# FN_001.net
KiCad netlist of a schematic drawn in EAGLE
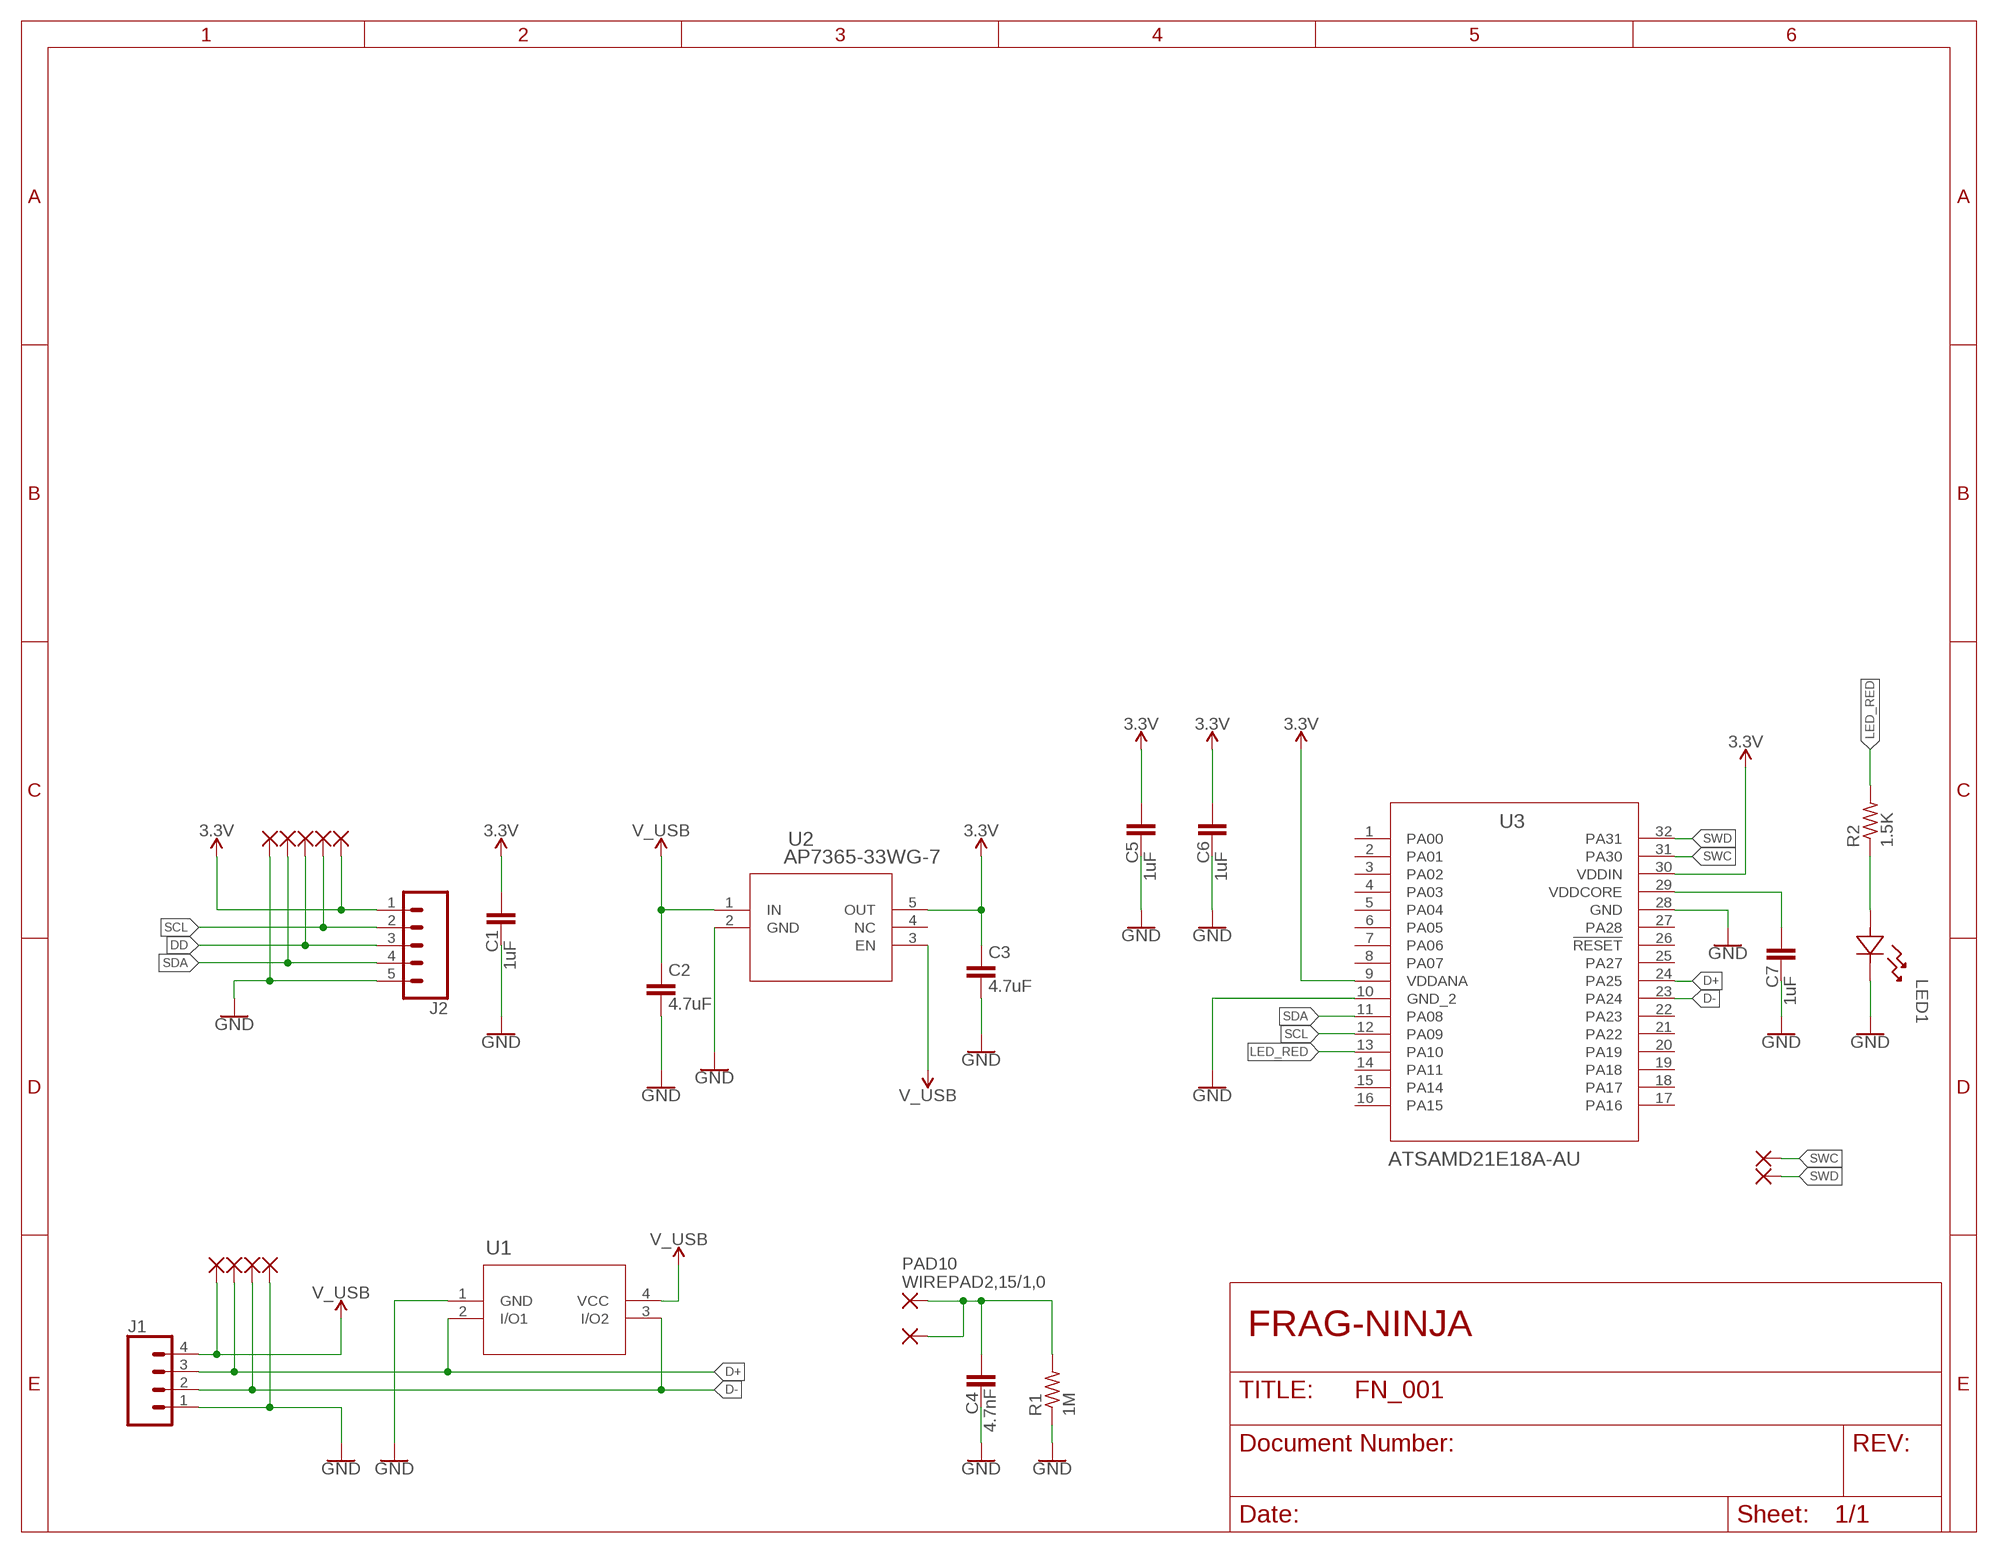
[diagram p0: schematic, sheet 1]

(export (version "E")
  (design (tool "Eeschema 10.0.6"))
  (components
    (comp (ref "C1")
      (value "1uF")
      (footprint "eagle-import:C0603K")
      (libsource (lib "eagle-import") (part "C-EUC0603K"))
    )
    (comp (ref "C2")
      (value "4.7uF")
      (footprint "eagle-import:C0603K")
      (libsource (lib "eagle-import") (part "C-EUC0603K"))
    )
    (comp (ref "C3")
      (value "4.7uF")
      (footprint "eagle-import:C0603K")
      (libsource (lib "eagle-import") (part "C-EUC0603K"))
    )
    (comp (ref "C4")
      (value "4.7nF")
      (footprint "eagle-import:C0603K")
      (libsource (lib "eagle-import") (part "C-EUC0603K"))
    )
    (comp (ref "C5")
      (value "1uF")
      (footprint "eagle-import:C0603K")
      (libsource (lib "eagle-import") (part "C-EUC0603K"))
    )
    (comp (ref "C6")
      (value "1uF")
      (footprint "eagle-import:C0603K")
      (libsource (lib "eagle-import") (part "C-EUC0603K"))
    )
    (comp (ref "C7")
      (value "1uF")
      (footprint "eagle-import:C0603K")
      (libsource (lib "eagle-import") (part "C-EUC0603K"))
    )
    (comp (ref "J1")
      (value "CONN_04PTH")
      (footprint "eagle-import:1X04")
      (libsource (lib "eagle-import") (part "CONN_04PTH"))
    )
    (comp (ref "J2")
      (value "CONN_05")
      (footprint "eagle-import:1X05")
      (libsource (lib "eagle-import") (part "CONN_05"))
    )
    (comp (ref "LED1")
      (value "SML-D12U1WT86")
      (footprint "eagle-import:LED_SMLD12_ROM")
      (fields (field (name "COPYRIGHT") "Copyright (C) 2018 Accelerated Designs. All rights reserved"))
      (libsource (lib "eagle-import") (part "SML-D12U1WT86"))
    )
    (comp (ref "PAD1")
      (value "WIREPADSMD1,27-254")
      (footprint "eagle-import:SMD1,27-2,54")
      (libsource (lib "eagle-import") (part "WIREPADSMD1,27-254"))
    )
    (comp (ref "PAD2")
      (value "WIREPADSMD1,27-254")
      (footprint "eagle-import:SMD1,27-2,54")
      (libsource (lib "eagle-import") (part "WIREPADSMD1,27-254"))
    )
    (comp (ref "PAD3")
      (value "WIREPADSMD1,27-254")
      (footprint "eagle-import:SMD1,27-2,54")
      (libsource (lib "eagle-import") (part "WIREPADSMD1,27-254"))
    )
    (comp (ref "PAD4")
      (value "WIREPADSMD1,27-254")
      (footprint "eagle-import:SMD1,27-2,54")
      (libsource (lib "eagle-import") (part "WIREPADSMD1,27-254"))
    )
    (comp (ref "PAD5")
      (value "WIREPADSMD1,27-254")
      (footprint "eagle-import:SMD1,27-2,54")
      (libsource (lib "eagle-import") (part "WIREPADSMD1,27-254"))
    )
    (comp (ref "PAD6")
      (value "WIREPADSMD1,27-254")
      (footprint "eagle-import:SMD1,27-2,54")
      (libsource (lib "eagle-import") (part "WIREPADSMD1,27-254"))
    )
    (comp (ref "PAD7")
      (value "WIREPADSMD1,27-254")
      (footprint "eagle-import:SMD1,27-2,54")
      (libsource (lib "eagle-import") (part "WIREPADSMD1,27-254"))
    )
    (comp (ref "PAD8")
      (value "WIREPADSMD1,27-254")
      (footprint "eagle-import:SMD1,27-2,54")
      (libsource (lib "eagle-import") (part "WIREPADSMD1,27-254"))
    )
    (comp (ref "PAD9")
      (value "WIREPADSMD1,27-254")
      (footprint "eagle-import:SMD1,27-2,54")
      (libsource (lib "eagle-import") (part "WIREPADSMD1,27-254"))
    )
    (comp (ref "PAD10")
      (value "WIREPAD2,15/1,0")
      (footprint "eagle-import:2,15_1,0")
      (libsource (lib "eagle-import") (part "WIREPAD2,15/1,0"))
    )
    (comp (ref "PAD11")
      (value "WIREPADSMD2,54-5,08")
      (footprint "eagle-import:SMD2,54-5,08")
      (libsource (lib "eagle-import") (part "WIREPADSMD2,54-5,08"))
    )
    (comp (ref "PAD12")
      (value "WIREPADSMD1,27-254")
      (footprint "eagle-import:SMD1,27-2,54")
      (libsource (lib "eagle-import") (part "WIREPADSMD1,27-254"))
    )
    (comp (ref "PAD13")
      (value "WIREPADSMD1,27-254")
      (footprint "eagle-import:SMD1,27-2,54")
      (libsource (lib "eagle-import") (part "WIREPADSMD1,27-254"))
    )
    (comp (ref "R1")
      (value "1M")
      (footprint "eagle-import:R0603")
      (libsource (lib "eagle-import") (part "R-US_R0603"))
    )
    (comp (ref "R2")
      (value "1.5K")
      (footprint "eagle-import:R0603")
      (libsource (lib "eagle-import") (part "R-US_R0603"))
    )
    (comp (ref "U1")
      (value "PRTR5V0U2X")
      (footprint "eagle-import:SOT143B_NXP")
      (libsource (lib "eagle-import") (part "PRTR5V0U2X"))
    )
    (comp (ref "U2")
      (value "AP7365-33WG-7")
      (footprint "eagle-import:SOT25_DIO")
      (libsource (lib "eagle-import") (part "AP7365-33WG-7"))
    )
    (comp (ref "U3")
      (value "ATSAMD21E18A-AU")
      (footprint "eagle-import:TQFP32_MC_MCH")
      (fields (field (name "COPYRIGHT") "Copyright (C) 2018 Accelerated Designs. All rights reserved"))
      (libsource (lib "eagle-import") (part "ATSAMD21E18A-AU"))
    )
  )
  (nets
    (net (code "1") (name "3.3V") (class "Default")
      (node (ref "C1") (pin "1") (pinfunction "1_1") (pintype "passive"))
      (node (ref "C3") (pin "1") (pinfunction "1_1") (pintype "passive"))
      (node (ref "C5") (pin "1") (pinfunction "1_1") (pintype "passive"))
      (node (ref "C6") (pin "1") (pinfunction "1_1") (pintype "passive"))
      (node (ref "J2") (pin "1") (pinfunction "1_1") (pintype "passive"))
      (node (ref "PAD9") (pin "1") (pinfunction "P_1") (pintype "passive"))
      (node (ref "U2") (pin "5") (pinfunction "OUT_5") (pintype "output"))
      (node (ref "U3") (pin "30") (pinfunction "VDDIN_30") (pintype "power_in"))
      (node (ref "U3") (pin "9") (pinfunction "VDDANA_9") (pintype "power_in"))
    )
    (net (code "2") (name "D+") (class "Default")
      (node (ref "J1") (pin "3") (pinfunction "3_3") (pintype "passive"))
      (node (ref "PAD2") (pin "1") (pinfunction "P_1") (pintype "passive"))
      (node (ref "U1") (pin "2") (pinfunction "I/O1_2") (pintype "passive"))
      (node (ref "U3") (pin "24") (pinfunction "PA25_24") (pintype "bidirectional"))
    )
    (net (code "3") (name "D-") (class "Default")
      (node (ref "J1") (pin "2") (pinfunction "2_2") (pintype "passive"))
      (node (ref "PAD3") (pin "1") (pinfunction "P_1") (pintype "passive"))
      (node (ref "U1") (pin "3") (pinfunction "I/O2_3") (pintype "passive"))
      (node (ref "U3") (pin "23") (pinfunction "PA24_23") (pintype "bidirectional"))
    )
    (net (code "4") (name "DD") (class "Default")
      (node (ref "J2") (pin "3") (pinfunction "3_3") (pintype "passive"))
      (node (ref "PAD7") (pin "1") (pinfunction "P_1") (pintype "passive"))
    )
    (net (code "5") (name "GND") (class "Default")
      (node (ref "C1") (pin "2") (pinfunction "2_2") (pintype "passive"))
      (node (ref "C2") (pin "2") (pinfunction "2_2") (pintype "passive"))
      (node (ref "C3") (pin "2") (pinfunction "2_2") (pintype "passive"))
      (node (ref "C4") (pin "2") (pinfunction "2_2") (pintype "passive"))
      (node (ref "C5") (pin "2") (pinfunction "2_2") (pintype "passive"))
      (node (ref "C6") (pin "2") (pinfunction "2_2") (pintype "passive"))
      (node (ref "C7") (pin "2") (pinfunction "2_2") (pintype "passive"))
      (node (ref "J1") (pin "1") (pinfunction "1_1") (pintype "passive"))
      (node (ref "J2") (pin "5") (pinfunction "5_5") (pintype "passive"))
      (node (ref "LED1") (pin "1") (pinfunction "1_1") (pintype "passive"))
      (node (ref "PAD4") (pin "1") (pinfunction "P_1") (pintype "passive"))
      (node (ref "PAD5") (pin "1") (pinfunction "P_1") (pintype "passive"))
      (node (ref "R1") (pin "1") (pinfunction "1_1") (pintype "passive"))
      (node (ref "U1") (pin "1") (pinfunction "GND_1") (pintype "passive"))
      (node (ref "U2") (pin "2") (pinfunction "GND_2") (pintype "power_in"))
      (node (ref "U3") (pin "10") (pinfunction "GND_2_10") (pintype "passive"))
      (node (ref "U3") (pin "28") (pinfunction "GND_28") (pintype "passive"))
    )
    (net (code "6") (name "LED_RED") (class "Default")
      (node (ref "R2") (pin "2") (pinfunction "2_2") (pintype "passive"))
      (node (ref "U3") (pin "13") (pinfunction "PA10_13") (pintype "bidirectional"))
    )
    (net (code "7") (name "Net-(LED1-Pad2)") (class "Default")
      (node (ref "LED1") (pin "2") (pinfunction "2_2") (pintype "passive"))
      (node (ref "R2") (pin "1") (pinfunction "1_1") (pintype "passive"))
    )
    (net (code "8") (name "Net-(PAD10-P)") (class "Default")
      (node (ref "C4") (pin "1") (pinfunction "1_1") (pintype "passive"))
      (node (ref "PAD10") (pin "1") (pinfunction "P_1") (pintype "passive"))
      (node (ref "PAD11") (pin "1") (pinfunction "P_1") (pintype "passive"))
      (node (ref "R1") (pin "2") (pinfunction "2_2") (pintype "passive"))
    )
    (net (code "9") (name "Net-(U3-VDDCORE)") (class "Default")
      (node (ref "C7") (pin "1") (pinfunction "1_1") (pintype "passive"))
      (node (ref "U3") (pin "29") (pinfunction "VDDCORE_29") (pintype "power_in"))
    )
    (net (code "10") (name "SCL") (class "Default")
      (node (ref "J2") (pin "2") (pinfunction "2_2") (pintype "passive"))
      (node (ref "PAD8") (pin "1") (pinfunction "P_1") (pintype "passive"))
      (node (ref "U3") (pin "12") (pinfunction "PA09_12") (pintype "bidirectional"))
    )
    (net (code "11") (name "SDA") (class "Default")
      (node (ref "J2") (pin "4") (pinfunction "4_4") (pintype "passive"))
      (node (ref "PAD6") (pin "1") (pinfunction "P_1") (pintype "passive"))
      (node (ref "U3") (pin "11") (pinfunction "PA08_11") (pintype "bidirectional"))
    )
    (net (code "12") (name "SWC") (class "Default")
      (node (ref "PAD12") (pin "1") (pinfunction "P_1") (pintype "passive"))
      (node (ref "U3") (pin "31") (pinfunction "PA30_31") (pintype "bidirectional"))
    )
    (net (code "13") (name "SWD") (class "Default")
      (node (ref "PAD13") (pin "1") (pinfunction "P_1") (pintype "passive"))
      (node (ref "U3") (pin "32") (pinfunction "PA31_32") (pintype "bidirectional"))
    )
    (net (code "14") (name "V_USB") (class "Default")
      (node (ref "C2") (pin "1") (pinfunction "1_1") (pintype "passive"))
      (node (ref "J1") (pin "4") (pinfunction "4_4") (pintype "passive"))
      (node (ref "PAD1") (pin "1") (pinfunction "P_1") (pintype "passive"))
      (node (ref "U1") (pin "4") (pinfunction "VCC_4") (pintype "passive"))
      (node (ref "U2") (pin "1") (pinfunction "IN_1") (pintype "input"))
      (node (ref "U2") (pin "3") (pinfunction "EN_3") (pintype "input"))
    )
    (net (code "15") (name "unconnected-(U2-NC-Pad4)") (class "Default")
      (node (ref "U2") (pin "4") (pinfunction "NC_4") (pintype "no_connect"))
    )
    (net (code "16") (name "unconnected-(U3-PA00-Pad1)") (class "Default")
      (node (ref "U3") (pin "1") (pinfunction "PA00_1") (pintype "bidirectional"))
    )
    (net (code "17") (name "unconnected-(U3-PA01-Pad2)") (class "Default")
      (node (ref "U3") (pin "2") (pinfunction "PA01_2") (pintype "bidirectional"))
    )
    (net (code "18") (name "unconnected-(U3-PA02-Pad3)") (class "Default")
      (node (ref "U3") (pin "3") (pinfunction "PA02_3") (pintype "bidirectional"))
    )
    (net (code "19") (name "unconnected-(U3-PA03-Pad4)") (class "Default")
      (node (ref "U3") (pin "4") (pinfunction "PA03_4") (pintype "bidirectional"))
    )
    (net (code "20") (name "unconnected-(U3-PA04-Pad5)") (class "Default")
      (node (ref "U3") (pin "5") (pinfunction "PA04_5") (pintype "bidirectional"))
    )
    (net (code "21") (name "unconnected-(U3-PA05-Pad6)") (class "Default")
      (node (ref "U3") (pin "6") (pinfunction "PA05_6") (pintype "bidirectional"))
    )
    (net (code "22") (name "unconnected-(U3-PA06-Pad7)") (class "Default")
      (node (ref "U3") (pin "7") (pinfunction "PA06_7") (pintype "bidirectional"))
    )
    (net (code "23") (name "unconnected-(U3-PA07-Pad8)") (class "Default")
      (node (ref "U3") (pin "8") (pinfunction "PA07_8") (pintype "bidirectional"))
    )
    (net (code "24") (name "unconnected-(U3-PA11-Pad14)") (class "Default")
      (node (ref "U3") (pin "14") (pinfunction "PA11_14") (pintype "bidirectional"))
    )
    (net (code "25") (name "unconnected-(U3-PA14-Pad15)") (class "Default")
      (node (ref "U3") (pin "15") (pinfunction "PA14_15") (pintype "bidirectional"))
    )
    (net (code "26") (name "unconnected-(U3-PA15-Pad16)") (class "Default")
      (node (ref "U3") (pin "16") (pinfunction "PA15_16") (pintype "bidirectional"))
    )
    (net (code "27") (name "unconnected-(U3-PA16-Pad17)") (class "Default")
      (node (ref "U3") (pin "17") (pinfunction "PA16_17") (pintype "bidirectional"))
    )
    (net (code "28") (name "unconnected-(U3-PA17-Pad18)") (class "Default")
      (node (ref "U3") (pin "18") (pinfunction "PA17_18") (pintype "bidirectional"))
    )
    (net (code "29") (name "unconnected-(U3-PA18-Pad19)") (class "Default")
      (node (ref "U3") (pin "19") (pinfunction "PA18_19") (pintype "bidirectional"))
    )
    (net (code "30") (name "unconnected-(U3-PA19-Pad20)") (class "Default")
      (node (ref "U3") (pin "20") (pinfunction "PA19_20") (pintype "bidirectional"))
    )
    (net (code "31") (name "unconnected-(U3-PA22-Pad21)") (class "Default")
      (node (ref "U3") (pin "21") (pinfunction "PA22_21") (pintype "bidirectional"))
    )
    (net (code "32") (name "unconnected-(U3-PA23-Pad22)") (class "Default")
      (node (ref "U3") (pin "22") (pinfunction "PA23_22") (pintype "bidirectional"))
    )
    (net (code "33") (name "unconnected-(U3-PA27-Pad25)") (class "Default")
      (node (ref "U3") (pin "25") (pinfunction "PA27_25") (pintype "bidirectional"))
    )
    (net (code "34") (name "unconnected-(U3-PA28-Pad27)") (class "Default")
      (node (ref "U3") (pin "27") (pinfunction "PA28_27") (pintype "bidirectional"))
    )
    (net (code "35") (name "unconnected-(U3-~{RESET}-Pad26)") (class "Default")
      (node (ref "U3") (pin "26") (pinfunction "~{RESET}_26") (pintype "passive"))
    )
  )
)
